# month-led-r1.net
KiCad netlist of a schematic drawn in EAGLE
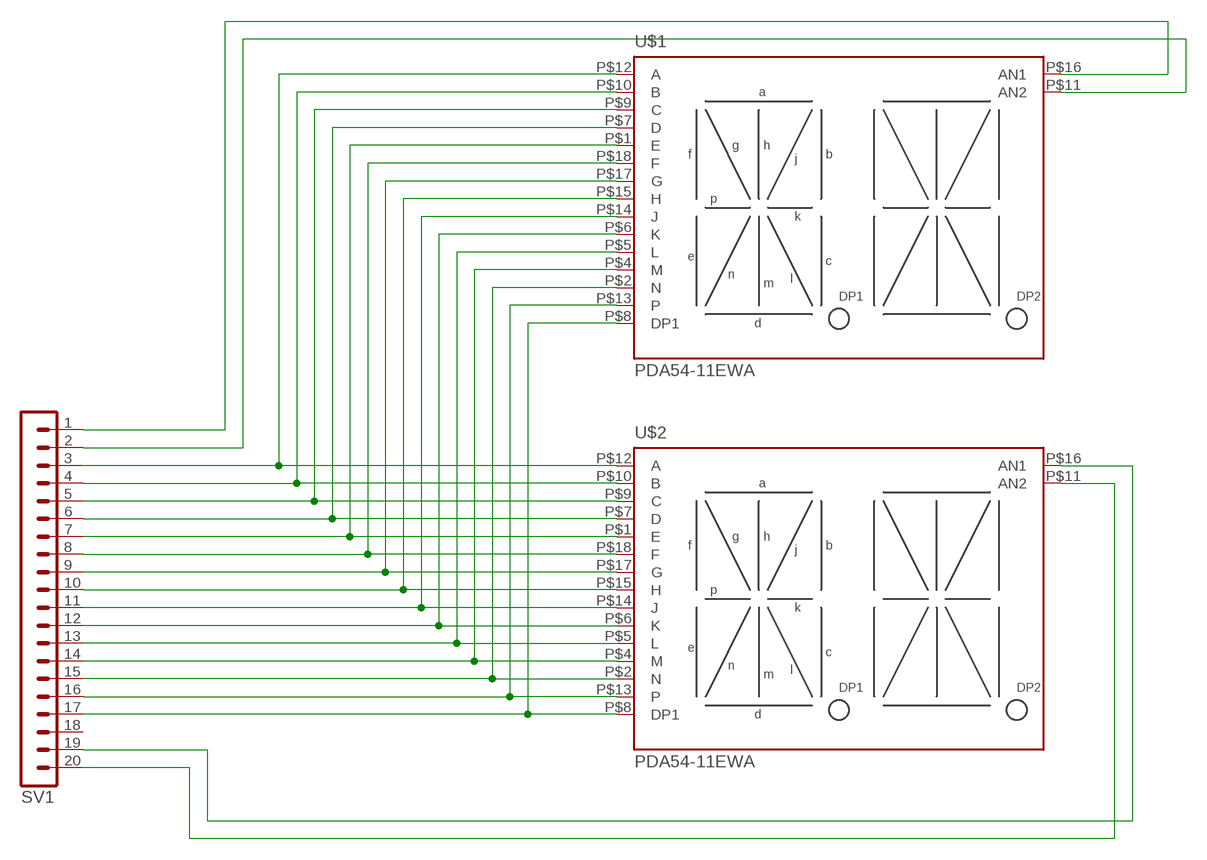
[diagram p0: schematic, sheet 1]

(export (version "E")
  (design (tool "Eeschema 10.0.6"))
  (components
    (comp (ref "SV1")
      (value "MA20-1W")
      (footprint "eagle-import:MA20-1W")
      (libsource (lib "eagle-import") (part "MA20-1W"))
    )
    (comp (ref "U$1")
      (value "PDA54-11EWA")
      (footprint "eagle-import:PDA54-11XX")
      (libsource (lib "eagle-import") (part "PDA54-11EWA"))
    )
    (comp (ref "U$2")
      (value "PDA54-11EWA")
      (footprint "eagle-import:PDA54-11XX")
      (libsource (lib "eagle-import") (part "PDA54-11EWA"))
    )
  )
  (nets
    (net (code "1") (name "Net-(U$1-A)") (class "Default")
      (node (ref "SV1") (pin "3") (pinfunction "3_3") (pintype "passive"))
      (node (ref "U$1") (pin "P$12") (pinfunction "A_P$12") (pintype "passive"))
      (node (ref "U$2") (pin "P$12") (pinfunction "A_P$12") (pintype "passive"))
    )
    (net (code "2") (name "Net-(U$1-AN1)") (class "Default")
      (node (ref "SV1") (pin "1") (pinfunction "1_1") (pintype "passive"))
      (node (ref "U$1") (pin "P$16") (pinfunction "AN1_P$16") (pintype "passive"))
    )
    (net (code "3") (name "Net-(U$1-AN2)") (class "Default")
      (node (ref "SV1") (pin "2") (pinfunction "2_2") (pintype "passive"))
      (node (ref "U$1") (pin "P$11") (pinfunction "AN2_P$11") (pintype "passive"))
    )
    (net (code "4") (name "Net-(U$1-B)") (class "Default")
      (node (ref "SV1") (pin "4") (pinfunction "4_4") (pintype "passive"))
      (node (ref "U$1") (pin "P$10") (pinfunction "B_P$10") (pintype "passive"))
      (node (ref "U$2") (pin "P$10") (pinfunction "B_P$10") (pintype "passive"))
    )
    (net (code "5") (name "Net-(U$1-C)") (class "Default")
      (node (ref "SV1") (pin "5") (pinfunction "5_5") (pintype "passive"))
      (node (ref "U$1") (pin "P$9") (pinfunction "C_P$9") (pintype "passive"))
      (node (ref "U$2") (pin "P$9") (pinfunction "C_P$9") (pintype "passive"))
    )
    (net (code "6") (name "Net-(U$1-D)") (class "Default")
      (node (ref "SV1") (pin "6") (pinfunction "6_6") (pintype "passive"))
      (node (ref "U$1") (pin "P$7") (pinfunction "D_P$7") (pintype "passive"))
      (node (ref "U$2") (pin "P$7") (pinfunction "D_P$7") (pintype "passive"))
    )
    (net (code "7") (name "Net-(U$1-DP1)") (class "Default")
      (node (ref "SV1") (pin "17") (pinfunction "17_17") (pintype "passive"))
      (node (ref "U$1") (pin "P$8") (pinfunction "DP1_P$8") (pintype "passive"))
      (node (ref "U$2") (pin "P$8") (pinfunction "DP1_P$8") (pintype "passive"))
    )
    (net (code "8") (name "Net-(U$1-E)") (class "Default")
      (node (ref "SV1") (pin "7") (pinfunction "7_7") (pintype "passive"))
      (node (ref "U$1") (pin "P$1") (pinfunction "E_P$1") (pintype "passive"))
      (node (ref "U$2") (pin "P$1") (pinfunction "E_P$1") (pintype "passive"))
    )
    (net (code "9") (name "Net-(U$1-F)") (class "Default")
      (node (ref "SV1") (pin "8") (pinfunction "8_8") (pintype "passive"))
      (node (ref "U$1") (pin "P$18") (pinfunction "F_P$18") (pintype "passive"))
      (node (ref "U$2") (pin "P$18") (pinfunction "F_P$18") (pintype "passive"))
    )
    (net (code "10") (name "Net-(U$1-G)") (class "Default")
      (node (ref "SV1") (pin "9") (pinfunction "9_9") (pintype "passive"))
      (node (ref "U$1") (pin "P$17") (pinfunction "G_P$17") (pintype "passive"))
      (node (ref "U$2") (pin "P$17") (pinfunction "G_P$17") (pintype "passive"))
    )
    (net (code "11") (name "Net-(U$1-H)") (class "Default")
      (node (ref "SV1") (pin "10") (pinfunction "10_10") (pintype "passive"))
      (node (ref "U$1") (pin "P$15") (pinfunction "H_P$15") (pintype "passive"))
      (node (ref "U$2") (pin "P$15") (pinfunction "H_P$15") (pintype "passive"))
    )
    (net (code "12") (name "Net-(U$1-J)") (class "Default")
      (node (ref "SV1") (pin "11") (pinfunction "11_11") (pintype "passive"))
      (node (ref "U$1") (pin "P$14") (pinfunction "J_P$14") (pintype "passive"))
      (node (ref "U$2") (pin "P$14") (pinfunction "J_P$14") (pintype "passive"))
    )
    (net (code "13") (name "Net-(U$1-K)") (class "Default")
      (node (ref "SV1") (pin "12") (pinfunction "12_12") (pintype "passive"))
      (node (ref "U$1") (pin "P$6") (pinfunction "K_P$6") (pintype "passive"))
      (node (ref "U$2") (pin "P$6") (pinfunction "K_P$6") (pintype "passive"))
    )
    (net (code "14") (name "Net-(U$1-L)") (class "Default")
      (node (ref "SV1") (pin "13") (pinfunction "13_13") (pintype "passive"))
      (node (ref "U$1") (pin "P$5") (pinfunction "L_P$5") (pintype "passive"))
      (node (ref "U$2") (pin "P$5") (pinfunction "L_P$5") (pintype "passive"))
    )
    (net (code "15") (name "Net-(U$1-M)") (class "Default")
      (node (ref "SV1") (pin "14") (pinfunction "14_14") (pintype "passive"))
      (node (ref "U$1") (pin "P$4") (pinfunction "M_P$4") (pintype "passive"))
      (node (ref "U$2") (pin "P$4") (pinfunction "M_P$4") (pintype "passive"))
    )
    (net (code "16") (name "Net-(U$1-N)") (class "Default")
      (node (ref "SV1") (pin "15") (pinfunction "15_15") (pintype "passive"))
      (node (ref "U$1") (pin "P$2") (pinfunction "N_P$2") (pintype "passive"))
      (node (ref "U$2") (pin "P$2") (pinfunction "N_P$2") (pintype "passive"))
    )
    (net (code "17") (name "Net-(U$1-P)") (class "Default")
      (node (ref "SV1") (pin "16") (pinfunction "16_16") (pintype "passive"))
      (node (ref "U$1") (pin "P$13") (pinfunction "P_P$13") (pintype "passive"))
      (node (ref "U$2") (pin "P$13") (pinfunction "P_P$13") (pintype "passive"))
    )
    (net (code "18") (name "Net-(U$2-AN1)") (class "Default")
      (node (ref "SV1") (pin "19") (pinfunction "19_19") (pintype "passive"))
      (node (ref "U$2") (pin "P$16") (pinfunction "AN1_P$16") (pintype "passive"))
    )
    (net (code "19") (name "Net-(U$2-AN2)") (class "Default")
      (node (ref "SV1") (pin "20") (pinfunction "20_20") (pintype "passive"))
      (node (ref "U$2") (pin "P$11") (pinfunction "AN2_P$11") (pintype "passive"))
    )
    (net (code "20") (name "unconnected-(SV1-Pad18)") (class "Default")
      (node (ref "SV1") (pin "18") (pinfunction "18_18") (pintype "passive"))
    )
  )
)
